# 70cm_13cm_diplexer.net
KiCad netlist of a schematic drawn in Altium Designer
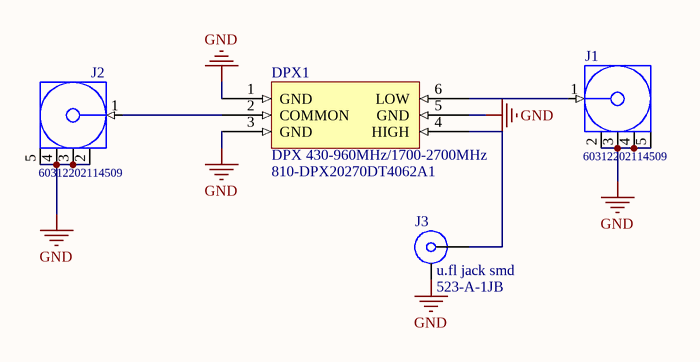
[diagram p0: 70cm_13cm_diplexer.SchDoc]

(export (version "E")
  (design (tool "Eeschema 10.0.6"))
  (components
    (comp (ref "DPX1")
      (value "DPX 430-960MHz/1700-2700MHz")
      (footprint "1.6x0.8mm [EIA 0603]")
      (description "Diplexer 430-960MHz/1700-2700MHz 0603")
      (fields
        (field (name "MANUFACTURER") "TDK")
        (field (name "MANUFACTURER PART NUMBER") "DPX202700DT-4062A1")
        (field (name "SUPPLIER PART NUMBER 1") "810-DPX20270DT4062A1")
      )
      (libsource (lib "ftg_lib") (part "DPX202700DT-4062A1"))
    )
    (comp (ref "J1")
      (value "60312202114509")
      (footprint "60312202114509")
      (description "WR-SMA SMA PCB End Launch Jack Round Post for 1.6 mm PCB")
      (fields (field (name "PUBLISHER") "Wurth Elektronik"))
      (libsource (lib "Altium_WR-SMA (rev18b)") (part "60312202114509"))
    )
    (comp (ref "J2")
      (value "60312202114509")
      (footprint "60312202114509")
      (description "WR-SMA SMA PCB End Launch Jack Round Post for 1.6 mm PCB")
      (fields (field (name "PUBLISHER") "Wurth Elektronik"))
      (libsource (lib "Altium_WR-SMA (rev18b)") (part "60312202114509"))
    )
    (comp (ref "J3")
      (value "u.fl jack smd")
      (footprint "U.FL jack")
      (fields (field (name "SUPPLIER PART NUMBER 1") "523-A-1JB"))
      (libsource (lib "ftg_lib") (part "u.fl connector, jack A-1JB"))
    )
  )
  (nets
    (net (code "1") (name "GND") (class "Default")
      (node (ref "DPX1") (pin "1") (pinfunction "GND_1") (pintype "input"))
      (node (ref "DPX1") (pin "3") (pinfunction "GND_3") (pintype "input"))
      (node (ref "DPX1") (pin "5") (pinfunction "GND_5") (pintype "input"))
      (node (ref "J1") (pin "2") (pinfunction "GND_2") (pintype "power_in"))
      (node (ref "J1") (pin "3") (pinfunction "GND_3") (pintype "power_in"))
      (node (ref "J1") (pin "4") (pinfunction "GND_4") (pintype "power_in"))
      (node (ref "J1") (pin "5") (pinfunction "GND_5") (pintype "power_in"))
      (node (ref "J2") (pin "2") (pinfunction "GND_2") (pintype "power_in"))
      (node (ref "J2") (pin "3") (pinfunction "GND_3") (pintype "power_in"))
      (node (ref "J2") (pin "4") (pinfunction "GND_4") (pintype "power_in"))
      (node (ref "J2") (pin "5") (pinfunction "GND_5") (pintype "power_in"))
      (node (ref "J3") (pin "2") (pinfunction "2_2") (pintype "passive"))
    )
    (net (code "2") (name "Net-(DPX1-COMMON)") (class "Default")
      (node (ref "DPX1") (pin "2") (pinfunction "COMMON_2") (pintype "input"))
      (node (ref "J2") (pin "1") (pinfunction "Signal_1") (pintype "input"))
    )
    (net (code "3") (name "Net-(DPX1-HIGH)") (class "Default")
      (node (ref "DPX1") (pin "4") (pinfunction "HIGH_4") (pintype "input"))
      (node (ref "J3") (pin "1") (pinfunction "1_1") (pintype "passive"))
    )
    (net (code "4") (name "Net-(DPX1-LOW)") (class "Default")
      (node (ref "DPX1") (pin "6") (pinfunction "LOW_6") (pintype "input"))
      (node (ref "J1") (pin "1") (pinfunction "Signal_1") (pintype "input"))
    )
  )
)
